# Heltec_wifi_kit_32_breakout.net
KiCad netlist of a schematic drawn in EAGLE
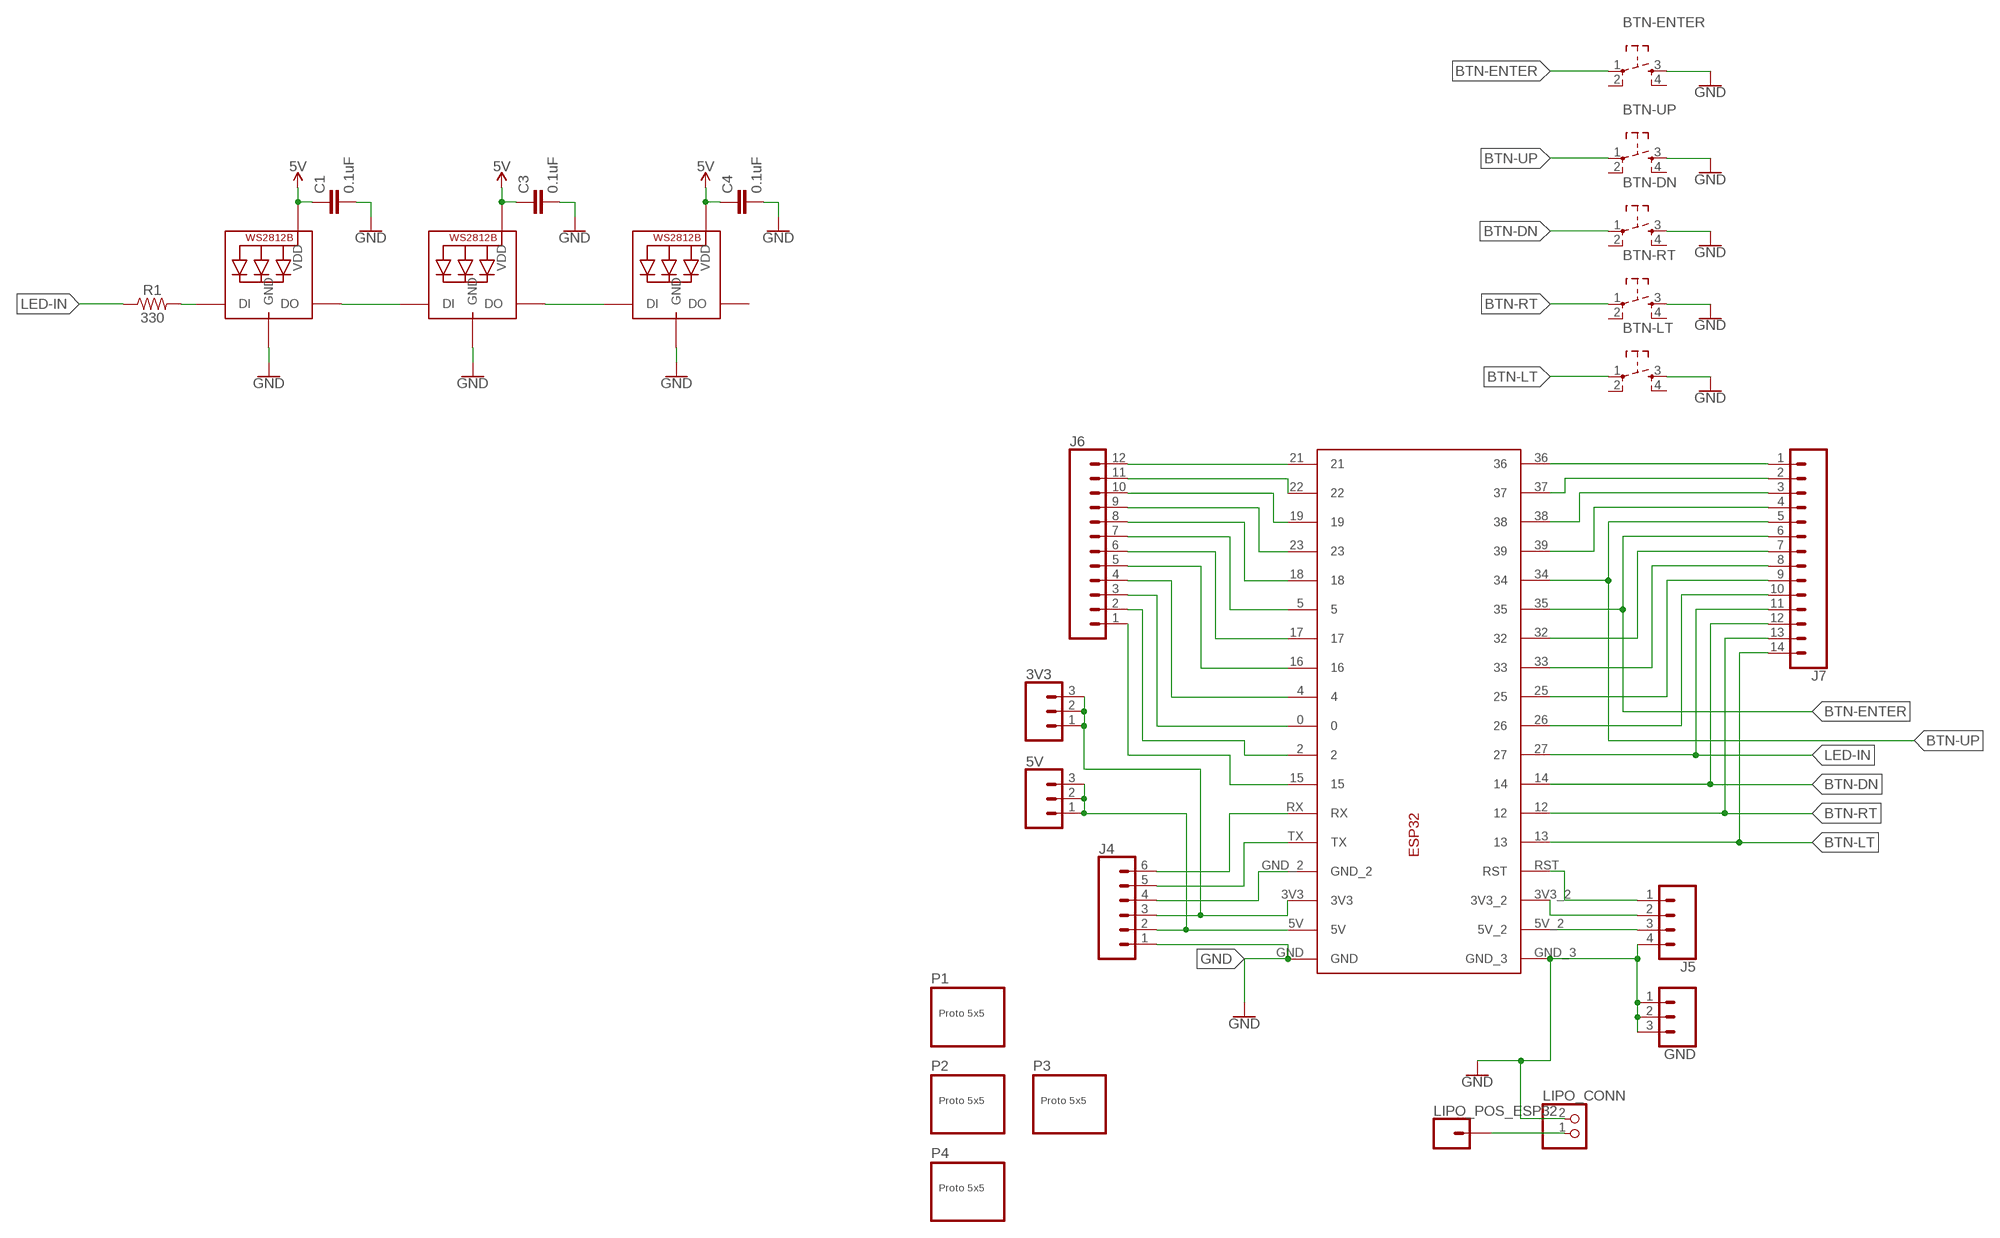
[diagram p0: schematic, sheet 1]

(export (version "E")
  (design (tool "Eeschema 10.0.6"))
  (components
    (comp (ref "3V3")
      (value "CONN_03")
      (footprint "eagle-import:1X03")
      (libsource (lib "eagle-import") (part "CONN_03"))
    )
    (comp (ref "5V")
      (value "CONN_03")
      (footprint "eagle-import:1X03")
      (libsource (lib "eagle-import") (part "CONN_03"))
    )
    (comp (ref "BTN-DN")
      (value "SW_TACT_4P")
      (footprint "eagle-import:SW_TACT_SMALL")
      (libsource (lib "eagle-import") (part "SW_TACT_4P"))
    )
    (comp (ref "BTN-ENTER")
      (value "SW_TACT_4P")
      (footprint "eagle-import:SW_TACT_SMALL")
      (libsource (lib "eagle-import") (part "SW_TACT_4P"))
    )
    (comp (ref "BTN-LT")
      (value "SW_TACT_4P")
      (footprint "eagle-import:SW_TACT_SMALL")
      (libsource (lib "eagle-import") (part "SW_TACT_4P"))
    )
    (comp (ref "BTN-RT")
      (value "SW_TACT_4P")
      (footprint "eagle-import:SW_TACT_SMALL")
      (libsource (lib "eagle-import") (part "SW_TACT_4P"))
    )
    (comp (ref "BTN-UP")
      (value "SW_TACT_4P")
      (footprint "eagle-import:SW_TACT_SMALL")
      (libsource (lib "eagle-import") (part "SW_TACT_4P"))
    )
    (comp (ref "C1")
      (value "0.1uF")
      (footprint "eagle-import:0603")
      (libsource (lib "eagle-import") (part "0.1UF-0603-25V-(+80/-20%)"))
    )
    (comp (ref "C3")
      (value "0.1uF")
      (footprint "eagle-import:0603")
      (libsource (lib "eagle-import") (part "0.1UF-0603-25V-(+80/-20%)"))
    )
    (comp (ref "C4")
      (value "0.1uF")
      (footprint "eagle-import:0603")
      (libsource (lib "eagle-import") (part "0.1UF-0603-25V-(+80/-20%)"))
    )
    (comp (ref "ESP32")
      (value "HELTEC-WIFI-KIT-32")
      (footprint "eagle-import:HELTEC-WIFI-KIT-32")
      (libsource (lib "eagle-import") (part "HELTEC-WIFI-KIT-32"))
    )
    (comp (ref "GND")
      (value "CONN_03")
      (footprint "eagle-import:1X03")
      (libsource (lib "eagle-import") (part "CONN_03"))
    )
    (comp (ref "J4")
      (value "CONN_06SILK_FEMALE_PTH")
      (footprint "eagle-import:1X06")
      (libsource (lib "eagle-import") (part "CONN_06SILK_FEMALE_PTH"))
    )
    (comp (ref "J5")
      (value "CONN_04")
      (footprint "eagle-import:1X04")
      (libsource (lib "eagle-import") (part "CONN_04"))
    )
    (comp (ref "J6")
      (value "CONN_12")
      (footprint "eagle-import:1X12")
      (libsource (lib "eagle-import") (part "CONN_12"))
    )
    (comp (ref "J7")
      (value "CONN_14")
      (footprint "eagle-import:1X14")
      (libsource (lib "eagle-import") (part "CONN_14"))
    )
    (comp (ref "LED2")
      (value "WS2812B5050")
      (footprint "eagle-import:WS2812B")
      (libsource (lib "eagle-import") (part "WS2812B5050"))
    )
    (comp (ref "LED3")
      (value "WS2812B5050")
      (footprint "eagle-import:WS2812B")
      (libsource (lib "eagle-import") (part "WS2812B5050"))
    )
    (comp (ref "LED7")
      (value "WS2812B5050")
      (footprint "eagle-import:WS2812B")
      (libsource (lib "eagle-import") (part "WS2812B5050"))
    )
    (comp (ref "LIPO_CONN")
      (value "JST_2PIN-THM-RA")
      (footprint "eagle-import:JST-PH-2-THM-RA")
      (libsource (lib "eagle-import") (part "JST_2PIN-THM-RA"))
    )
    (comp (ref "LIPO_POS_ESP32")
      (value "CONN_01")
      (footprint "eagle-import:1X01")
      (libsource (lib "eagle-import") (part "CONN_01"))
    )
    (comp (ref "P1")
      (value "PROTO_VIAS_05X05")
      (footprint "eagle-import:PROTO_VIAS_05X05")
      (libsource (lib "eagle-import") (part "PROTO_VIAS_05X05"))
    )
    (comp (ref "P2")
      (value "PROTO_VIAS_05X05")
      (footprint "eagle-import:PROTO_VIAS_05X05")
      (libsource (lib "eagle-import") (part "PROTO_VIAS_05X05"))
    )
    (comp (ref "P3")
      (value "PROTO_VIAS_05X05")
      (footprint "eagle-import:PROTO_VIAS_05X05")
      (libsource (lib "eagle-import") (part "PROTO_VIAS_05X05"))
    )
    (comp (ref "P4")
      (value "PROTO_VIAS_05X05")
      (footprint "eagle-import:PROTO_VIAS_05X05")
      (libsource (lib "eagle-import") (part "PROTO_VIAS_05X05"))
    )
    (comp (ref "R1")
      (value "330")
      (footprint "eagle-import:0603")
      (libsource (lib "eagle-import") (part "330OHM-0603-1/10W-1%"))
    )
  )
  (nets
    (net (code "1") (name "5V") (class "Default")
      (node (ref "C1") (pin "1") (pinfunction "1_1") (pintype "passive"))
      (node (ref "C3") (pin "1") (pinfunction "1_1") (pintype "passive"))
      (node (ref "C4") (pin "1") (pinfunction "1_1") (pintype "passive"))
      (node (ref "LED2") (pin "1-VDD") (pinfunction "VDD_1-VDD") (pintype "power_in"))
      (node (ref "LED3") (pin "1-VDD") (pinfunction "VDD_1-VDD") (pintype "power_in"))
      (node (ref "LED7") (pin "1-VDD") (pinfunction "VDD_1-VDD") (pintype "power_in"))
    )
    (net (code "2") (name "BTN-DN") (class "Default")
      (node (ref "BTN-DN") (pin "1") (pinfunction "1_1") (pintype "passive"))
      (node (ref "ESP32") (pin "14") (pinfunction "14_14") (pintype "bidirectional"))
      (node (ref "J7") (pin "12") (pinfunction "12_12") (pintype "passive"))
    )
    (net (code "3") (name "BTN-ENTER") (class "Default")
      (node (ref "BTN-ENTER") (pin "1") (pinfunction "1_1") (pintype "passive"))
      (node (ref "ESP32") (pin "35") (pinfunction "35_35") (pintype "bidirectional"))
      (node (ref "J7") (pin "6") (pinfunction "6_6") (pintype "passive"))
    )
    (net (code "4") (name "BTN-LT") (class "Default")
      (node (ref "BTN-LT") (pin "1") (pinfunction "1_1") (pintype "passive"))
      (node (ref "ESP32") (pin "13") (pinfunction "13_13") (pintype "bidirectional"))
      (node (ref "J7") (pin "14") (pinfunction "14_14") (pintype "passive"))
    )
    (net (code "5") (name "BTN-RT") (class "Default")
      (node (ref "BTN-RT") (pin "1") (pinfunction "1_1") (pintype "passive"))
      (node (ref "ESP32") (pin "12") (pinfunction "12_12") (pintype "bidirectional"))
      (node (ref "J7") (pin "13") (pinfunction "13_13") (pintype "passive"))
    )
    (net (code "6") (name "BTN-UP") (class "Default")
      (node (ref "BTN-UP") (pin "1") (pinfunction "1_1") (pintype "passive"))
      (node (ref "ESP32") (pin "34") (pinfunction "34_34") (pintype "bidirectional"))
      (node (ref "J7") (pin "5") (pinfunction "5_5") (pintype "passive"))
    )
    (net (code "7") (name "GND") (class "Default")
      (node (ref "BTN-DN") (pin "3") (pinfunction "3_3") (pintype "passive"))
      (node (ref "BTN-ENTER") (pin "3") (pinfunction "3_3") (pintype "passive"))
      (node (ref "BTN-LT") (pin "3") (pinfunction "3_3") (pintype "passive"))
      (node (ref "BTN-RT") (pin "3") (pinfunction "3_3") (pintype "passive"))
      (node (ref "BTN-UP") (pin "3") (pinfunction "3_3") (pintype "passive"))
      (node (ref "C1") (pin "2") (pinfunction "2_2") (pintype "passive"))
      (node (ref "C3") (pin "2") (pinfunction "2_2") (pintype "passive"))
      (node (ref "C4") (pin "2") (pinfunction "2_2") (pintype "passive"))
      (node (ref "ESP32") (pin "GND") (pinfunction "GND_GND") (pintype "bidirectional"))
      (node (ref "ESP32") (pin "GND_3") (pinfunction "GND_3_GND_3") (pintype "bidirectional"))
      (node (ref "GND") (pin "1") (pinfunction "1_1") (pintype "passive"))
      (node (ref "GND") (pin "2") (pinfunction "2_2") (pintype "passive"))
      (node (ref "GND") (pin "3") (pinfunction "3_3") (pintype "passive"))
      (node (ref "J4") (pin "1") (pinfunction "1_1") (pintype "passive"))
      (node (ref "J5") (pin "4") (pinfunction "4_4") (pintype "passive"))
      (node (ref "LED2") (pin "3-GND") (pinfunction "GND_3-GND") (pintype "power_in"))
      (node (ref "LED3") (pin "3-GND") (pinfunction "GND_3-GND") (pintype "power_in"))
      (node (ref "LED7") (pin "3-GND") (pinfunction "GND_3-GND") (pintype "power_in"))
      (node (ref "LIPO_CONN") (pin "2") (pinfunction "1_2") (pintype "passive"))
    )
    (net (code "8") (name "LED-IN") (class "Default")
      (node (ref "ESP32") (pin "27") (pinfunction "27_27") (pintype "bidirectional"))
      (node (ref "J7") (pin "11") (pinfunction "11_11") (pintype "passive"))
      (node (ref "R1") (pin "1") (pinfunction "1_1") (pintype "passive"))
    )
    (net (code "9") (name "Net-(3V3-Pad1)") (class "Default")
      (node (ref "3V3") (pin "1") (pinfunction "1_1") (pintype "passive"))
      (node (ref "3V3") (pin "2") (pinfunction "2_2") (pintype "passive"))
      (node (ref "3V3") (pin "3") (pinfunction "3_3") (pintype "passive"))
      (node (ref "ESP32") (pin "3V3") (pinfunction "3V3_3V3") (pintype "bidirectional"))
      (node (ref "J4") (pin "3") (pinfunction "3_3") (pintype "passive"))
    )
    (net (code "10") (name "Net-(5V-Pad1)") (class "Default")
      (node (ref "5V") (pin "1") (pinfunction "1_1") (pintype "passive"))
      (node (ref "5V") (pin "2") (pinfunction "2_2") (pintype "passive"))
      (node (ref "5V") (pin "3") (pinfunction "3_3") (pintype "passive"))
      (node (ref "ESP32") (pin "5V") (pinfunction "5V_5V") (pintype "bidirectional"))
      (node (ref "J4") (pin "2") (pinfunction "2_2") (pintype "passive"))
    )
    (net (code "11") (name "Net-(ESP32-Pad0)") (class "Default")
      (node (ref "ESP32") (pin "0") (pinfunction "0_0") (pintype "bidirectional"))
      (node (ref "J6") (pin "3") (pinfunction "3_3") (pintype "passive"))
    )
    (net (code "12") (name "Net-(ESP32-Pad2)") (class "Default")
      (node (ref "ESP32") (pin "2") (pinfunction "2_2") (pintype "bidirectional"))
      (node (ref "J6") (pin "2") (pinfunction "2_2") (pintype "passive"))
    )
    (net (code "13") (name "Net-(ESP32-Pad3V3_2)") (class "Default")
      (node (ref "ESP32") (pin "3V3_2") (pinfunction "3V3_2_3V3_2") (pintype "bidirectional"))
      (node (ref "J5") (pin "2") (pinfunction "2_2") (pintype "passive"))
    )
    (net (code "14") (name "Net-(ESP32-Pad4)") (class "Default")
      (node (ref "ESP32") (pin "4") (pinfunction "4_4") (pintype "bidirectional"))
      (node (ref "J6") (pin "4") (pinfunction "4_4") (pintype "passive"))
    )
    (net (code "15") (name "Net-(ESP32-Pad5)") (class "Default")
      (node (ref "ESP32") (pin "5") (pinfunction "5_5") (pintype "bidirectional"))
      (node (ref "J6") (pin "7") (pinfunction "7_7") (pintype "passive"))
    )
    (net (code "16") (name "Net-(ESP32-Pad5V_2)") (class "Default")
      (node (ref "ESP32") (pin "5V_2") (pinfunction "5V_2_5V_2") (pintype "bidirectional"))
      (node (ref "J5") (pin "3") (pinfunction "3_3") (pintype "passive"))
    )
    (net (code "17") (name "Net-(ESP32-Pad15)") (class "Default")
      (node (ref "ESP32") (pin "15") (pinfunction "15_15") (pintype "bidirectional"))
      (node (ref "J6") (pin "1") (pinfunction "1_1") (pintype "passive"))
    )
    (net (code "18") (name "Net-(ESP32-Pad16)") (class "Default")
      (node (ref "ESP32") (pin "16") (pinfunction "16_16") (pintype "bidirectional"))
      (node (ref "J6") (pin "5") (pinfunction "5_5") (pintype "passive"))
    )
    (net (code "19") (name "Net-(ESP32-Pad17)") (class "Default")
      (node (ref "ESP32") (pin "17") (pinfunction "17_17") (pintype "bidirectional"))
      (node (ref "J6") (pin "6") (pinfunction "6_6") (pintype "passive"))
    )
    (net (code "20") (name "Net-(ESP32-Pad18)") (class "Default")
      (node (ref "ESP32") (pin "18") (pinfunction "18_18") (pintype "bidirectional"))
      (node (ref "J6") (pin "8") (pinfunction "8_8") (pintype "passive"))
    )
    (net (code "21") (name "Net-(ESP32-Pad19)") (class "Default")
      (node (ref "ESP32") (pin "19") (pinfunction "19_19") (pintype "bidirectional"))
      (node (ref "J6") (pin "10") (pinfunction "10_10") (pintype "passive"))
    )
    (net (code "22") (name "Net-(ESP32-Pad21)") (class "Default")
      (node (ref "ESP32") (pin "21") (pinfunction "21_21") (pintype "bidirectional"))
      (node (ref "J6") (pin "12") (pinfunction "12_12") (pintype "passive"))
    )
    (net (code "23") (name "Net-(ESP32-Pad22)") (class "Default")
      (node (ref "ESP32") (pin "22") (pinfunction "22_22") (pintype "bidirectional"))
      (node (ref "J6") (pin "11") (pinfunction "11_11") (pintype "passive"))
    )
    (net (code "24") (name "Net-(ESP32-Pad23)") (class "Default")
      (node (ref "ESP32") (pin "23") (pinfunction "23_23") (pintype "bidirectional"))
      (node (ref "J6") (pin "9") (pinfunction "9_9") (pintype "passive"))
    )
    (net (code "25") (name "Net-(ESP32-Pad25)") (class "Default")
      (node (ref "ESP32") (pin "25") (pinfunction "25_25") (pintype "bidirectional"))
      (node (ref "J7") (pin "9") (pinfunction "9_9") (pintype "passive"))
    )
    (net (code "26") (name "Net-(ESP32-Pad26)") (class "Default")
      (node (ref "ESP32") (pin "26") (pinfunction "26_26") (pintype "bidirectional"))
      (node (ref "J7") (pin "10") (pinfunction "10_10") (pintype "passive"))
    )
    (net (code "27") (name "Net-(ESP32-Pad32)") (class "Default")
      (node (ref "ESP32") (pin "32") (pinfunction "32_32") (pintype "bidirectional"))
      (node (ref "J7") (pin "7") (pinfunction "7_7") (pintype "passive"))
    )
    (net (code "28") (name "Net-(ESP32-Pad33)") (class "Default")
      (node (ref "ESP32") (pin "33") (pinfunction "33_33") (pintype "bidirectional"))
      (node (ref "J7") (pin "8") (pinfunction "8_8") (pintype "passive"))
    )
    (net (code "29") (name "Net-(ESP32-Pad36)") (class "Default")
      (node (ref "ESP32") (pin "36") (pinfunction "36_36") (pintype "bidirectional"))
      (node (ref "J7") (pin "1") (pinfunction "1_1") (pintype "passive"))
    )
    (net (code "30") (name "Net-(ESP32-Pad37)") (class "Default")
      (node (ref "ESP32") (pin "37") (pinfunction "37_37") (pintype "bidirectional"))
      (node (ref "J7") (pin "2") (pinfunction "2_2") (pintype "passive"))
    )
    (net (code "31") (name "Net-(ESP32-Pad38)") (class "Default")
      (node (ref "ESP32") (pin "38") (pinfunction "38_38") (pintype "bidirectional"))
      (node (ref "J7") (pin "3") (pinfunction "3_3") (pintype "passive"))
    )
    (net (code "32") (name "Net-(ESP32-Pad39)") (class "Default")
      (node (ref "ESP32") (pin "39") (pinfunction "39_39") (pintype "bidirectional"))
      (node (ref "J7") (pin "4") (pinfunction "4_4") (pintype "passive"))
    )
    (net (code "33") (name "Net-(ESP32-PadGND_2)") (class "Default")
      (node (ref "ESP32") (pin "GND_2") (pinfunction "GND_2_GND_2") (pintype "bidirectional"))
      (node (ref "J4") (pin "4") (pinfunction "4_4") (pintype "passive"))
    )
    (net (code "34") (name "Net-(ESP32-PadRST)") (class "Default")
      (node (ref "ESP32") (pin "RST") (pinfunction "RST_RST") (pintype "bidirectional"))
      (node (ref "J5") (pin "1") (pinfunction "1_1") (pintype "passive"))
    )
    (net (code "35") (name "Net-(ESP32-PadRX)") (class "Default")
      (node (ref "ESP32") (pin "RX") (pinfunction "RX_RX") (pintype "bidirectional"))
      (node (ref "J4") (pin "6") (pinfunction "6_6") (pintype "passive"))
    )
    (net (code "36") (name "Net-(ESP32-PadTX)") (class "Default")
      (node (ref "ESP32") (pin "TX") (pinfunction "TX_TX") (pintype "bidirectional"))
      (node (ref "J4") (pin "5") (pinfunction "5_5") (pintype "passive"))
    )
    (net (code "37") (name "Net-(LED2-DI)") (class "Default")
      (node (ref "LED2") (pin "4-DIN") (pinfunction "DI_4-DIN") (pintype "input"))
      (node (ref "LED7") (pin "2-DOUT") (pinfunction "DO_2-DOUT") (pintype "output"))
    )
    (net (code "38") (name "Net-(LED2-DO)") (class "Default")
      (node (ref "LED2") (pin "2-DOUT") (pinfunction "DO_2-DOUT") (pintype "output"))
      (node (ref "LED3") (pin "4-DIN") (pinfunction "DI_4-DIN") (pintype "input"))
    )
    (net (code "39") (name "Net-(LED7-DI)") (class "Default")
      (node (ref "LED7") (pin "4-DIN") (pinfunction "DI_4-DIN") (pintype "input"))
      (node (ref "R1") (pin "2") (pinfunction "2_2") (pintype "passive"))
    )
    (net (code "40") (name "Net-(LIPO_CONN-2)") (class "Default")
      (node (ref "LIPO_CONN") (pin "1") (pinfunction "2_1") (pintype "passive"))
      (node (ref "LIPO_POS_ESP32") (pin "1") (pinfunction "1_1") (pintype "passive"))
    )
    (net (code "41") (name "unconnected-(BTN-DN-Pad2)") (class "Default")
      (node (ref "BTN-DN") (pin "2") (pinfunction "2_2") (pintype "passive"))
    )
    (net (code "42") (name "unconnected-(BTN-DN-Pad4)") (class "Default")
      (node (ref "BTN-DN") (pin "4") (pinfunction "4_4") (pintype "passive"))
    )
    (net (code "43") (name "unconnected-(BTN-ENTER-Pad2)") (class "Default")
      (node (ref "BTN-ENTER") (pin "2") (pinfunction "2_2") (pintype "passive"))
    )
    (net (code "44") (name "unconnected-(BTN-ENTER-Pad4)") (class "Default")
      (node (ref "BTN-ENTER") (pin "4") (pinfunction "4_4") (pintype "passive"))
    )
    (net (code "45") (name "unconnected-(BTN-LT-Pad2)") (class "Default")
      (node (ref "BTN-LT") (pin "2") (pinfunction "2_2") (pintype "passive"))
    )
    (net (code "46") (name "unconnected-(BTN-LT-Pad4)") (class "Default")
      (node (ref "BTN-LT") (pin "4") (pinfunction "4_4") (pintype "passive"))
    )
    (net (code "47") (name "unconnected-(BTN-RT-Pad2)") (class "Default")
      (node (ref "BTN-RT") (pin "2") (pinfunction "2_2") (pintype "passive"))
    )
    (net (code "48") (name "unconnected-(BTN-RT-Pad4)") (class "Default")
      (node (ref "BTN-RT") (pin "4") (pinfunction "4_4") (pintype "passive"))
    )
    (net (code "49") (name "unconnected-(BTN-UP-Pad2)") (class "Default")
      (node (ref "BTN-UP") (pin "2") (pinfunction "2_2") (pintype "passive"))
    )
    (net (code "50") (name "unconnected-(BTN-UP-Pad4)") (class "Default")
      (node (ref "BTN-UP") (pin "4") (pinfunction "4_4") (pintype "passive"))
    )
    (net (code "51") (name "unconnected-(LED3-DO-Pad2-DOUT)") (class "Default")
      (node (ref "LED3") (pin "2-DOUT") (pinfunction "DO_2-DOUT") (pintype "output"))
    )
  )
)
